# ArmBoardNew-New_Main_Board.net
KiCad netlist of a schematic drawn in EAGLE
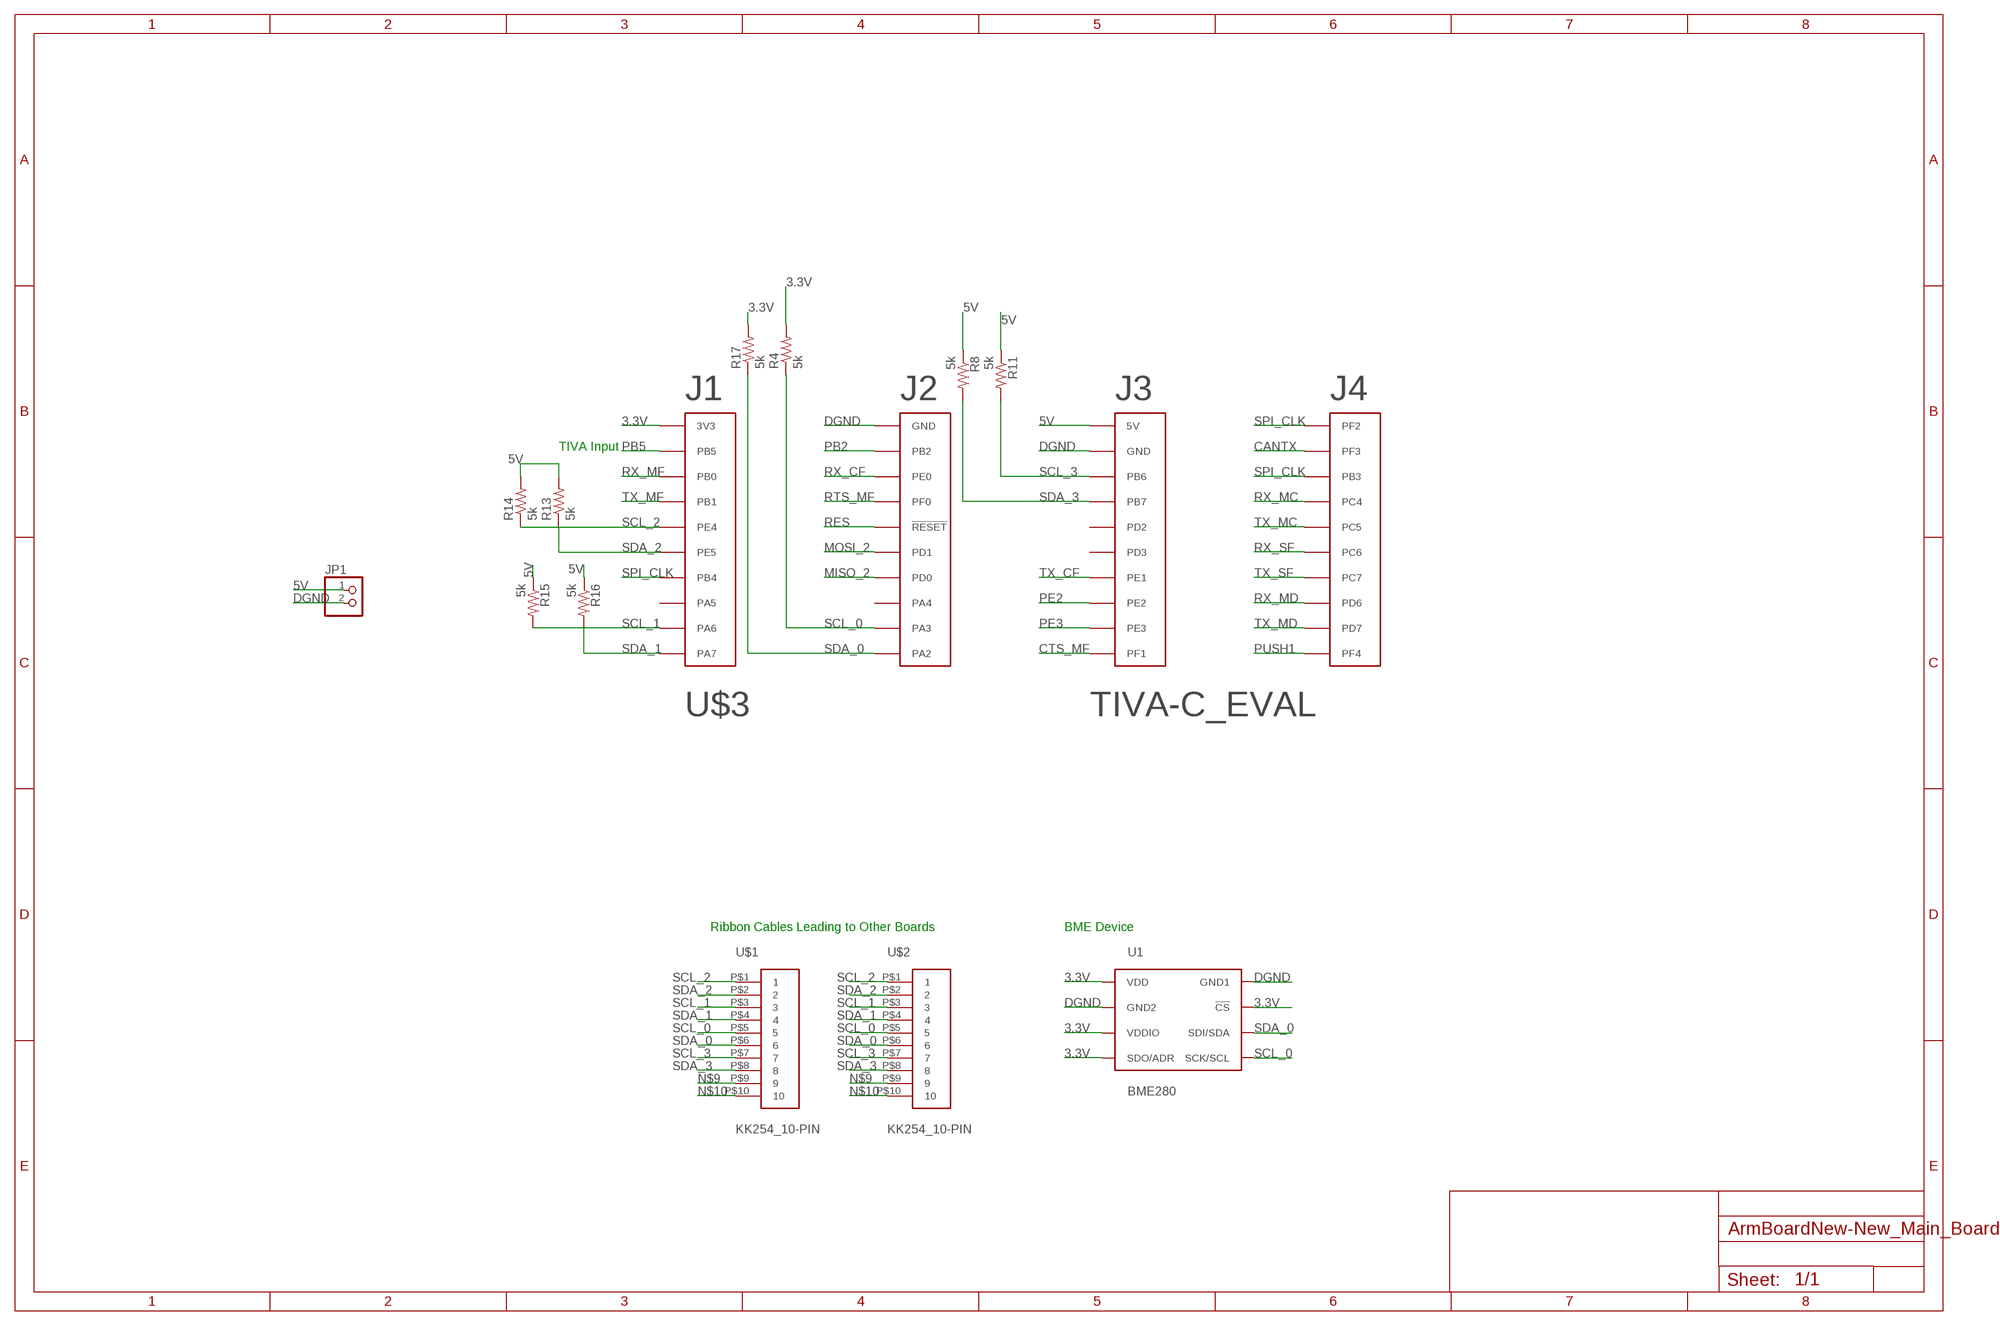
[diagram p0: schematic, sheet 1]

(export (version "E")
  (design (tool "Eeschema 10.0.6"))
  (components
    (comp (ref "JP1")
      (value "PINHD-1X2")
      (footprint "eagle-import:1X02")
      (libsource (lib "eagle-import") (part "PINHD-1X2"))
    )
    (comp (ref "R4")
      (value "5k")
      (footprint "eagle-import:R0805")
      (libsource (lib "eagle-import") (part "R-US_R0805"))
    )
    (comp (ref "R8")
      (value "5k")
      (footprint "eagle-import:R0805")
      (libsource (lib "eagle-import") (part "R-US_R0805"))
    )
    (comp (ref "R11")
      (value "5k")
      (footprint "eagle-import:R0805")
      (libsource (lib "eagle-import") (part "R-US_R0805"))
    )
    (comp (ref "R13")
      (value "5k")
      (footprint "eagle-import:R0805")
      (libsource (lib "eagle-import") (part "R-US_R0805"))
    )
    (comp (ref "R14")
      (value "5k")
      (footprint "eagle-import:R0805")
      (libsource (lib "eagle-import") (part "R-US_R0805"))
    )
    (comp (ref "R15")
      (value "5k")
      (footprint "eagle-import:R0805")
      (libsource (lib "eagle-import") (part "R-US_R0805"))
    )
    (comp (ref "R16")
      (value "5k")
      (footprint "eagle-import:R0805")
      (libsource (lib "eagle-import") (part "R-US_R0805"))
    )
    (comp (ref "R17")
      (value "5k")
      (footprint "eagle-import:R0805")
      (libsource (lib "eagle-import") (part "R-US_R0805"))
    )
    (comp (ref "U$1")
      (value "KK254_10-PIN")
      (footprint "eagle-import:KK254_10-PIN")
      (libsource (lib "eagle-import") (part "KK254_10-PIN"))
    )
    (comp (ref "U$2")
      (value "KK254_10-PIN")
      (footprint "eagle-import:KK254_10-PIN")
      (libsource (lib "eagle-import") (part "KK254_10-PIN"))
    )
    (comp (ref "U$3")
      (value "TIVA-C_EVAL")
      (footprint "eagle-import:TIVA-C_EVAL")
      (libsource (lib "eagle-import") (part "TIVA-C_EVAL"))
    )
    (comp (ref "U1")
      (value "BME280")
      (footprint "eagle-import:BME280_LGA")
      (libsource (lib "eagle-import") (part "BME280"))
    )
  )
  (nets
    (net (code "1") (name "/3.3V") (class "Default")
      (node (ref "R17") (pin "2") (pinfunction "2_2") (pintype "passive"))
      (node (ref "R4") (pin "2") (pinfunction "2_2") (pintype "passive"))
      (node (ref "U$3") (pin "1-1") (pinfunction "3V3_1-1") (pintype "bidirectional"))
      (node (ref "U1") (pin "P$2") (pinfunction "~{CS}_P$2") (pintype "bidirectional"))
      (node (ref "U1") (pin "P$5") (pinfunction "SDO/ADR_P$5") (pintype "bidirectional"))
      (node (ref "U1") (pin "P$6") (pinfunction "VDDIO_P$6") (pintype "bidirectional"))
      (node (ref "U1") (pin "P$8") (pinfunction "VDD_P$8") (pintype "bidirectional"))
    )
    (net (code "2") (name "/5V") (class "Default")
      (node (ref "JP1") (pin "1") (pinfunction "1_1") (pintype "passive"))
      (node (ref "R11") (pin "1") (pinfunction "1_1") (pintype "passive"))
      (node (ref "R13") (pin "2") (pinfunction "2_2") (pintype "passive"))
      (node (ref "R14") (pin "2") (pinfunction "2_2") (pintype "passive"))
      (node (ref "R15") (pin "1") (pinfunction "1_1") (pintype "passive"))
      (node (ref "R16") (pin "1") (pinfunction "1_1") (pintype "passive"))
      (node (ref "R8") (pin "1") (pinfunction "1_1") (pintype "passive"))
      (node (ref "U$3") (pin "3-1") (pinfunction "5V_3-1") (pintype "bidirectional"))
    )
    (net (code "3") (name "/CANTX") (class "Default")
      (node (ref "U$3") (pin "4-2") (pinfunction "PF3_4-2") (pintype "bidirectional"))
    )
    (net (code "4") (name "/CTS_MF") (class "Default")
      (node (ref "U$3") (pin "3-10") (pinfunction "PF1_3-10") (pintype "bidirectional"))
    )
    (net (code "5") (name "/DGND") (class "Default")
      (node (ref "JP1") (pin "2") (pinfunction "2_2") (pintype "passive"))
      (node (ref "U$3") (pin "2-1") (pinfunction "GND_2-1") (pintype "bidirectional"))
      (node (ref "U$3") (pin "3-2") (pinfunction "GND_3-2") (pintype "bidirectional"))
      (node (ref "U1") (pin "P$1") (pinfunction "GND1_P$1") (pintype "bidirectional"))
      (node (ref "U1") (pin "P$7") (pinfunction "GND2_P$7") (pintype "bidirectional"))
    )
    (net (code "6") (name "/MISO_2") (class "Default")
      (node (ref "U$3") (pin "2-7") (pinfunction "PD0_2-7") (pintype "bidirectional"))
    )
    (net (code "7") (name "/MOSI_2") (class "Default")
      (node (ref "U$3") (pin "2-6") (pinfunction "PD1_2-6") (pintype "bidirectional"))
    )
    (net (code "8") (name "/N$9") (class "Default")
      (node (ref "U$1") (pin "P$9") (pinfunction "9_P$9") (pintype "bidirectional"))
      (node (ref "U$2") (pin "P$9") (pinfunction "9_P$9") (pintype "bidirectional"))
    )
    (net (code "9") (name "/N$10") (class "Default")
      (node (ref "U$1") (pin "P$10") (pinfunction "10_P$10") (pintype "bidirectional"))
      (node (ref "U$2") (pin "P$10") (pinfunction "10_P$10") (pintype "bidirectional"))
    )
    (net (code "10") (name "/PB2") (class "Default")
      (node (ref "U$3") (pin "2-2") (pinfunction "PB2_2-2") (pintype "bidirectional"))
    )
    (net (code "11") (name "/PB5") (class "Default")
      (node (ref "U$3") (pin "1-2") (pinfunction "PB5_1-2") (pintype "bidirectional"))
    )
    (net (code "12") (name "/PE2") (class "Default")
      (node (ref "U$3") (pin "3-8") (pinfunction "PE2_3-8") (pintype "bidirectional"))
    )
    (net (code "13") (name "/PE3") (class "Default")
      (node (ref "U$3") (pin "3-9") (pinfunction "PE3_3-9") (pintype "bidirectional"))
    )
    (net (code "14") (name "/PUSH1") (class "Default")
      (node (ref "U$3") (pin "4-10") (pinfunction "PF4_4-10") (pintype "bidirectional"))
    )
    (net (code "15") (name "/RES") (class "Default")
      (node (ref "U$3") (pin "2-5") (pinfunction "~{RESET}_2-5") (pintype "bidirectional"))
    )
    (net (code "16") (name "/RTS_MF") (class "Default")
      (node (ref "U$3") (pin "2-4") (pinfunction "PF0_2-4") (pintype "bidirectional"))
    )
    (net (code "17") (name "/RX_CF") (class "Default")
      (node (ref "U$3") (pin "2-3") (pinfunction "PE0_2-3") (pintype "bidirectional"))
    )
    (net (code "18") (name "/RX_MC") (class "Default")
      (node (ref "U$3") (pin "4-4") (pinfunction "PC4_4-4") (pintype "bidirectional"))
    )
    (net (code "19") (name "/RX_MD") (class "Default")
      (node (ref "U$3") (pin "4-8") (pinfunction "PD6_4-8") (pintype "bidirectional"))
    )
    (net (code "20") (name "/RX_MF") (class "Default")
      (node (ref "U$3") (pin "1-3") (pinfunction "PB0_1-3") (pintype "bidirectional"))
    )
    (net (code "21") (name "/RX_SF") (class "Default")
      (node (ref "U$3") (pin "4-6") (pinfunction "PC6_4-6") (pintype "bidirectional"))
    )
    (net (code "22") (name "/SCL_0") (class "Default")
      (node (ref "R4") (pin "1") (pinfunction "1_1") (pintype "passive"))
      (node (ref "U$1") (pin "P$5") (pinfunction "5_P$5") (pintype "bidirectional"))
      (node (ref "U$2") (pin "P$5") (pinfunction "5_P$5") (pintype "bidirectional"))
      (node (ref "U$3") (pin "2-9") (pinfunction "PA3_2-9") (pintype "bidirectional"))
      (node (ref "U1") (pin "P$4") (pinfunction "SCK/SCL_P$4") (pintype "bidirectional"))
    )
    (net (code "23") (name "/SCL_1") (class "Default")
      (node (ref "R15") (pin "2") (pinfunction "2_2") (pintype "passive"))
      (node (ref "U$1") (pin "P$3") (pinfunction "3_P$3") (pintype "bidirectional"))
      (node (ref "U$2") (pin "P$3") (pinfunction "3_P$3") (pintype "bidirectional"))
      (node (ref "U$3") (pin "1-9") (pinfunction "PA6_1-9") (pintype "bidirectional"))
    )
    (net (code "24") (name "/SCL_2") (class "Default")
      (node (ref "R14") (pin "1") (pinfunction "1_1") (pintype "passive"))
      (node (ref "U$1") (pin "P$1") (pinfunction "1_P$1") (pintype "bidirectional"))
      (node (ref "U$2") (pin "P$1") (pinfunction "1_P$1") (pintype "bidirectional"))
      (node (ref "U$3") (pin "1-5") (pinfunction "PE4_1-5") (pintype "bidirectional"))
    )
    (net (code "25") (name "/SCL_3") (class "Default")
      (node (ref "R11") (pin "2") (pinfunction "2_2") (pintype "passive"))
      (node (ref "U$1") (pin "P$7") (pinfunction "7_P$7") (pintype "bidirectional"))
      (node (ref "U$2") (pin "P$7") (pinfunction "7_P$7") (pintype "bidirectional"))
      (node (ref "U$3") (pin "3-3") (pinfunction "PB6_3-3") (pintype "bidirectional"))
    )
    (net (code "26") (name "/SDA_0") (class "Default")
      (node (ref "R17") (pin "1") (pinfunction "1_1") (pintype "passive"))
      (node (ref "U$1") (pin "P$6") (pinfunction "6_P$6") (pintype "bidirectional"))
      (node (ref "U$2") (pin "P$6") (pinfunction "6_P$6") (pintype "bidirectional"))
      (node (ref "U$3") (pin "2-10") (pinfunction "PA2_2-10") (pintype "bidirectional"))
      (node (ref "U1") (pin "P$3") (pinfunction "SDI/SDA_P$3") (pintype "bidirectional"))
    )
    (net (code "27") (name "/SDA_1") (class "Default")
      (node (ref "R16") (pin "2") (pinfunction "2_2") (pintype "passive"))
      (node (ref "U$1") (pin "P$4") (pinfunction "4_P$4") (pintype "bidirectional"))
      (node (ref "U$2") (pin "P$4") (pinfunction "4_P$4") (pintype "bidirectional"))
      (node (ref "U$3") (pin "1-10") (pinfunction "PA7_1-10") (pintype "bidirectional"))
    )
    (net (code "28") (name "/SDA_2") (class "Default")
      (node (ref "R13") (pin "1") (pinfunction "1_1") (pintype "passive"))
      (node (ref "U$1") (pin "P$2") (pinfunction "2_P$2") (pintype "bidirectional"))
      (node (ref "U$2") (pin "P$2") (pinfunction "2_P$2") (pintype "bidirectional"))
      (node (ref "U$3") (pin "1-6") (pinfunction "PE5_1-6") (pintype "bidirectional"))
    )
    (net (code "29") (name "/SDA_3") (class "Default")
      (node (ref "R8") (pin "2") (pinfunction "2_2") (pintype "passive"))
      (node (ref "U$1") (pin "P$8") (pinfunction "8_P$8") (pintype "bidirectional"))
      (node (ref "U$2") (pin "P$8") (pinfunction "8_P$8") (pintype "bidirectional"))
      (node (ref "U$3") (pin "3-4") (pinfunction "PB7_3-4") (pintype "bidirectional"))
    )
    (net (code "30") (name "/SPI_CLK") (class "Default")
      (node (ref "U$3") (pin "1-7") (pinfunction "PB4_1-7") (pintype "bidirectional"))
      (node (ref "U$3") (pin "4-1") (pinfunction "PF2_4-1") (pintype "bidirectional"))
      (node (ref "U$3") (pin "4-3") (pinfunction "PB3_4-3") (pintype "bidirectional"))
    )
    (net (code "31") (name "/TX_CF") (class "Default")
      (node (ref "U$3") (pin "3-7") (pinfunction "PE1_3-7") (pintype "bidirectional"))
    )
    (net (code "32") (name "/TX_MC") (class "Default")
      (node (ref "U$3") (pin "4-5") (pinfunction "PC5_4-5") (pintype "bidirectional"))
    )
    (net (code "33") (name "/TX_MD") (class "Default")
      (node (ref "U$3") (pin "4-9") (pinfunction "PD7_4-9") (pintype "bidirectional"))
    )
    (net (code "34") (name "/TX_MF") (class "Default")
      (node (ref "U$3") (pin "1-4") (pinfunction "PB1_1-4") (pintype "bidirectional"))
    )
    (net (code "35") (name "/TX_SF") (class "Default")
      (node (ref "U$3") (pin "4-7") (pinfunction "PC7_4-7") (pintype "bidirectional"))
    )
    (net (code "36") (name "unconnected-(U$3-PA4-Pad2-8)") (class "Default")
      (node (ref "U$3") (pin "2-8") (pinfunction "PA4_2-8") (pintype "bidirectional"))
    )
    (net (code "37") (name "unconnected-(U$3-PA5-Pad1-8)") (class "Default")
      (node (ref "U$3") (pin "1-8") (pinfunction "PA5_1-8") (pintype "bidirectional"))
    )
    (net (code "38") (name "unconnected-(U$3-PD2-Pad3-5)") (class "Default")
      (node (ref "U$3") (pin "3-5") (pinfunction "PD2_3-5") (pintype "bidirectional"))
    )
    (net (code "39") (name "unconnected-(U$3-PD3-Pad3-6)") (class "Default")
      (node (ref "U$3") (pin "3-6") (pinfunction "PD3_3-6") (pintype "bidirectional"))
    )
  )
)
